# Sheet1.net
KiCad netlist of a schematic drawn in Altium Designer
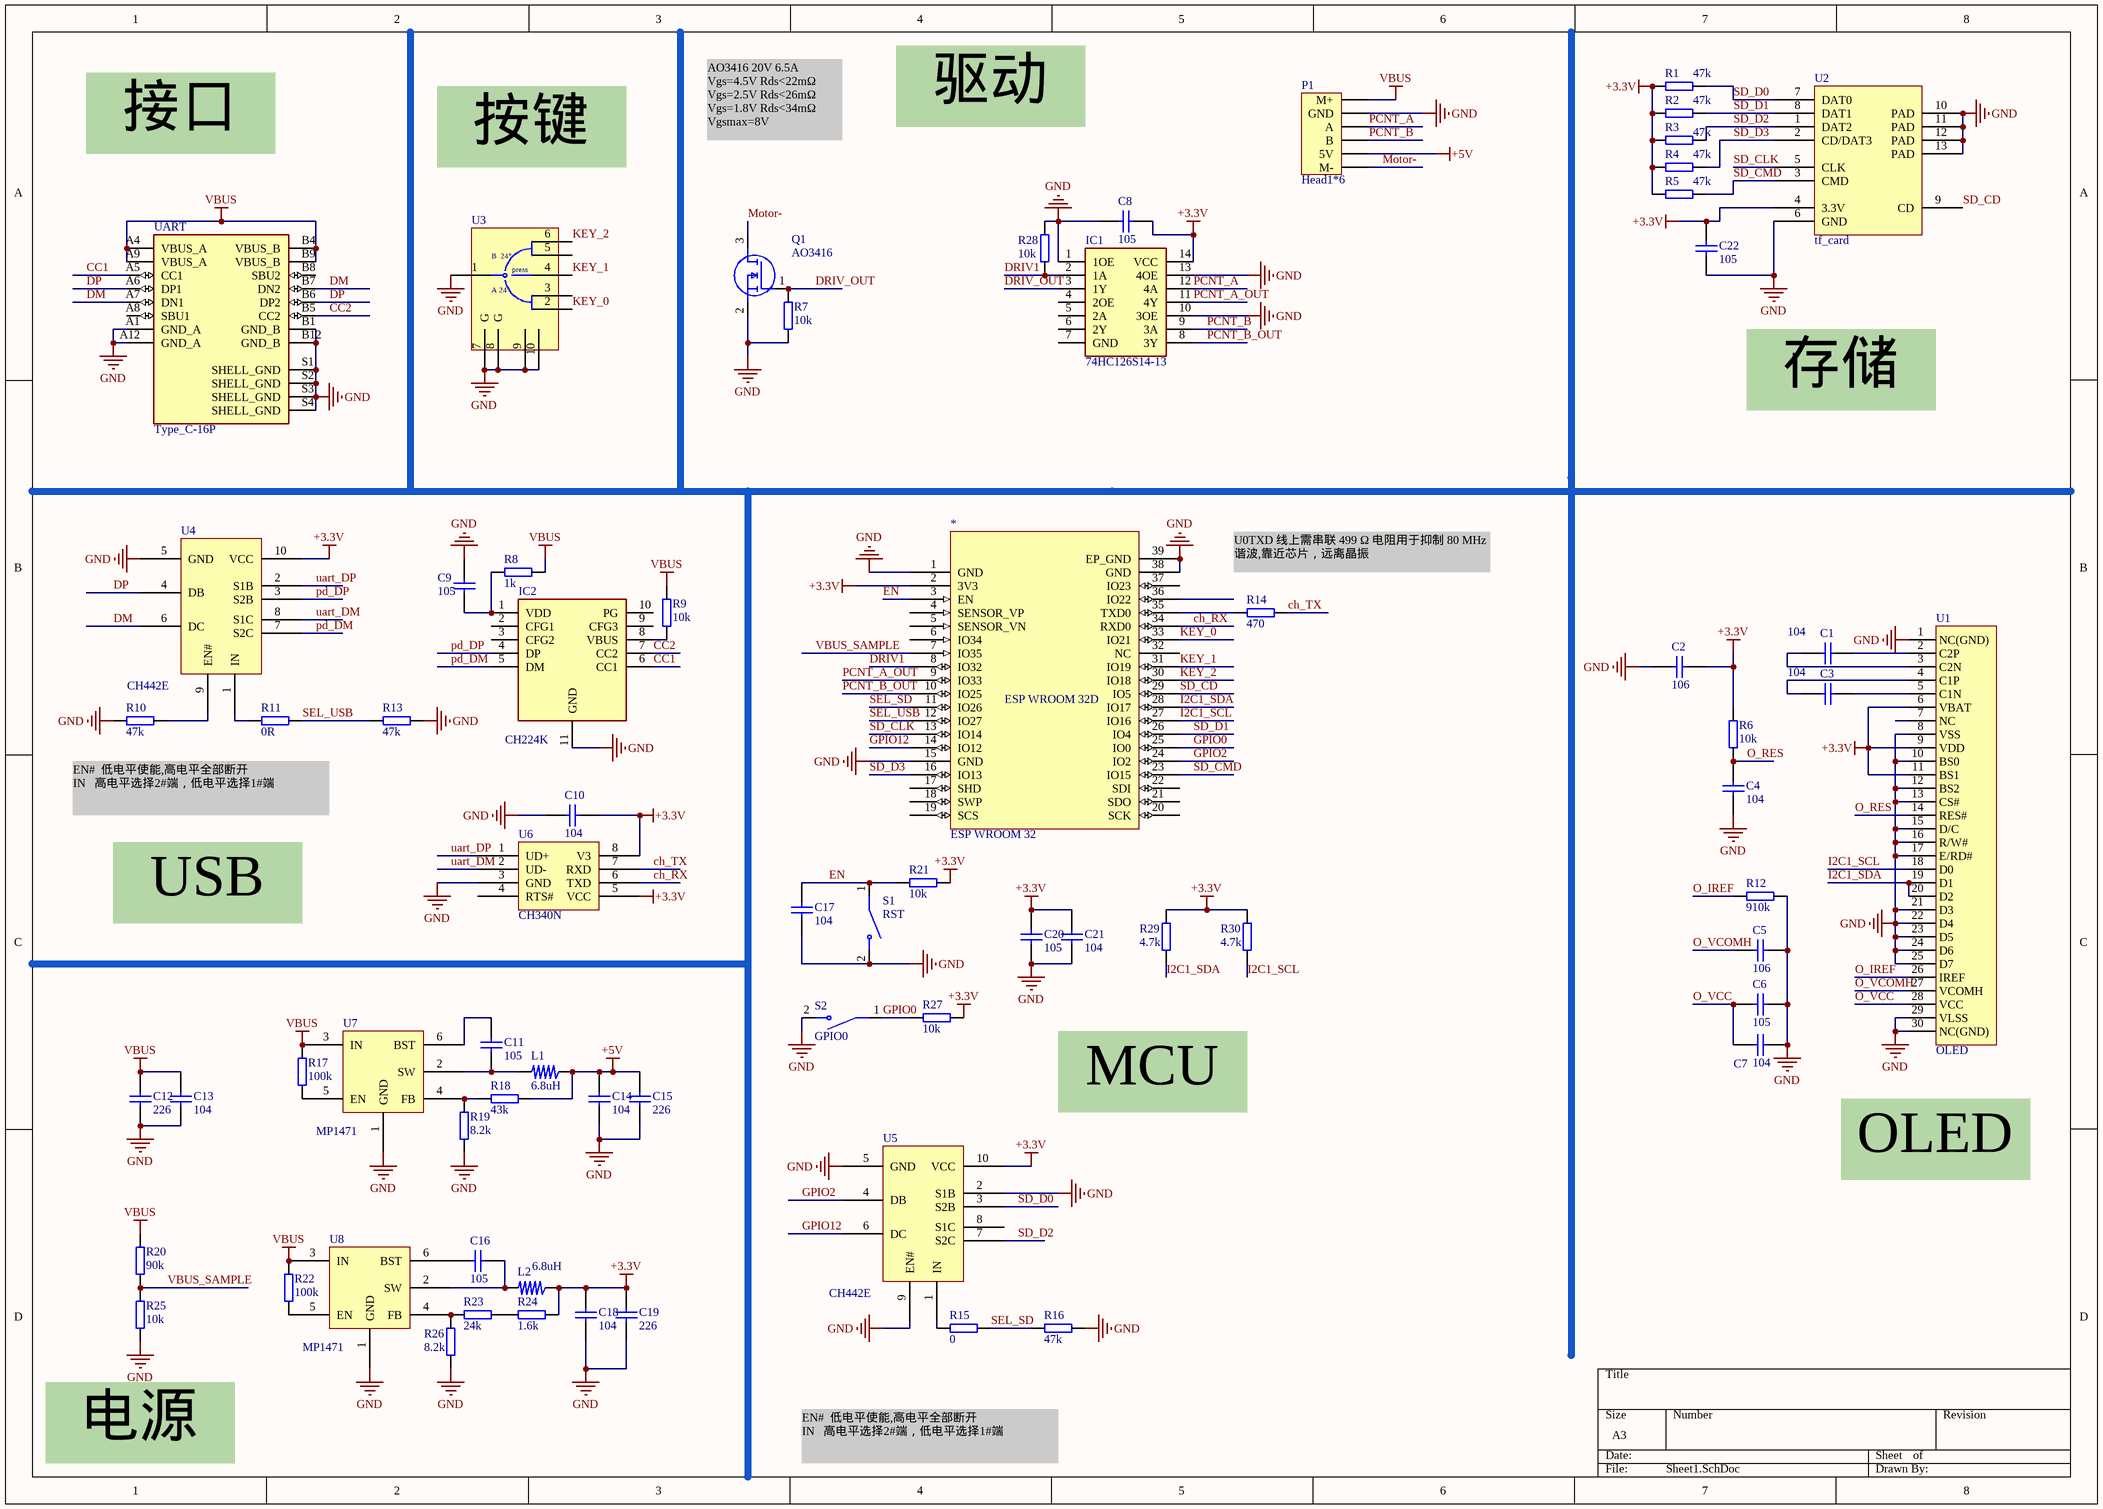
[diagram p0: Sheet1.SchDoc]

(export (version "E")
  (design (tool "Eeschema 10.0.6"))
  (components
    (comp (ref "*")
      (value "ESP WROOM 32")
      (footprint "ESP32-WROOM-32D")
      (libsource (lib "BuildDev") (part "ESP WROOM 32"))
    )
    (comp (ref "C1")
      (value "104")
      (footprint "CAPC1608[0603]")
      (description "Chip Capacitor, PSpice Model")
      (fields
        (field (name "TOLERANCE") "Y5V")
        (field (name "VOLTAGE") "3V")
        (field (name "PUBLISHER") "Altium Limited")
      )
      (libsource (lib "!)Miscellaneous Integrated Library") (part "Cap Chip 1"))
    )
    (comp (ref "C2")
      (value "106")
      (footprint "CAPC1608[0603]")
      (description "Chip Capacitor, PSpice Model")
      (fields
        (field (name "TOLERANCE") "Y5V")
        (field (name "VOLTAGE") "3V")
        (field (name "PUBLISHER") "Altium Limited")
      )
      (libsource (lib "!)Miscellaneous Integrated Library") (part "Cap Chip 1"))
    )
    (comp (ref "C3")
      (value "104")
      (footprint "CAPC1608[0603]")
      (description "Chip Capacitor, PSpice Model")
      (fields
        (field (name "TOLERANCE") "Y5V")
        (field (name "VOLTAGE") "3V")
        (field (name "PUBLISHER") "Altium Limited")
      )
      (libsource (lib "!)Miscellaneous Integrated Library") (part "Cap Chip 1"))
    )
    (comp (ref "C4")
      (value "104")
      (footprint "CAPC1608[0603]")
      (description "Chip Capacitor, PSpice Model")
      (fields
        (field (name "TOLERANCE") "Y5V")
        (field (name "VOLTAGE") "3V")
        (field (name "PUBLISHER") "Altium Limited")
      )
      (libsource (lib "!)Miscellaneous Integrated Library") (part "Cap Chip 1"))
    )
    (comp (ref "C5")
      (value "106")
      (footprint "CAPC1608[0603]")
      (description "Chip Capacitor, PSpice Model")
      (fields
        (field (name "TOLERANCE") "Y5V")
        (field (name "VOLTAGE") "3V")
        (field (name "PUBLISHER") "Altium Limited")
      )
      (libsource (lib "!)Miscellaneous Integrated Library") (part "Cap Chip 1"))
    )
    (comp (ref "C6")
      (value "105")
      (footprint "CAPC1608[0603]")
      (description "Chip Capacitor, PSpice Model")
      (fields
        (field (name "TOLERANCE") "Y5V")
        (field (name "VOLTAGE") "3V")
        (field (name "PUBLISHER") "Altium Limited")
      )
      (libsource (lib "!)Miscellaneous Integrated Library") (part "Cap Chip 1"))
    )
    (comp (ref "C7")
      (value "104")
      (footprint "CAPC1608[0603]")
      (description "Chip Capacitor, PSpice Model")
      (fields
        (field (name "TOLERANCE") "Y5V")
        (field (name "VOLTAGE") "3V")
        (field (name "PUBLISHER") "Altium Limited")
      )
      (libsource (lib "!)Miscellaneous Integrated Library") (part "Cap Chip 1"))
    )
    (comp (ref "C8")
      (value "105")
      (footprint "CAPC1608[0603]")
      (description "Chip Capacitor, PSpice Model")
      (fields
        (field (name "TOLERANCE") "Y5V")
        (field (name "VOLTAGE") "3V")
        (field (name "PUBLISHER") "Altium Limited")
      )
      (libsource (lib "!)Miscellaneous Integrated Library") (part "Cap Chip 1"))
    )
    (comp (ref "C9")
      (value "105")
      (footprint "CAPC1608[0603]")
      (description "Chip Capacitor, PSpice Model")
      (fields
        (field (name "TOLERANCE") "Y5V")
        (field (name "VOLTAGE") "3V")
        (field (name "PUBLISHER") "Altium Limited")
      )
      (libsource (lib "!)Miscellaneous Integrated Library") (part "Cap Chip 1"))
    )
    (comp (ref "C10")
      (value "104")
      (footprint "CAPC1608[0603]")
      (description "Chip Capacitor, PSpice Model")
      (fields
        (field (name "TOLERANCE") "Y5V")
        (field (name "VOLTAGE") "3V")
        (field (name "PUBLISHER") "Altium Limited")
      )
      (libsource (lib "!)Miscellaneous Integrated Library") (part "Cap Chip 1"))
    )
    (comp (ref "C11")
      (value "105")
      (footprint "CAPC1608[0603]")
      (description "Chip Capacitor, PSpice Model")
      (fields
        (field (name "TOLERANCE") "Y5V")
        (field (name "VOLTAGE") "3V")
        (field (name "PUBLISHER") "Altium Limited")
      )
      (libsource (lib "!)Miscellaneous Integrated Library") (part "Cap Chip 1"))
    )
    (comp (ref "C12")
      (value "226")
      (footprint "CAPC1608[0603]")
      (description "Chip Capacitor, PSpice Model")
      (fields
        (field (name "TOLERANCE") "Y5V")
        (field (name "VOLTAGE") "3V")
        (field (name "PUBLISHER") "Altium Limited")
      )
      (libsource (lib "!)Miscellaneous Integrated Library") (part "Cap Chip 1"))
    )
    (comp (ref "C13")
      (value "104")
      (footprint "CAPC1608[0603]")
      (description "Chip Capacitor, PSpice Model")
      (fields
        (field (name "TOLERANCE") "Y5V")
        (field (name "VOLTAGE") "3V")
        (field (name "PUBLISHER") "Altium Limited")
      )
      (libsource (lib "!)Miscellaneous Integrated Library") (part "Cap Chip 1"))
    )
    (comp (ref "C14")
      (value "104")
      (footprint "CAPC1608[0603]")
      (description "Chip Capacitor, PSpice Model")
      (fields
        (field (name "TOLERANCE") "Y5V")
        (field (name "VOLTAGE") "3V")
        (field (name "PUBLISHER") "Altium Limited")
      )
      (libsource (lib "!)Miscellaneous Integrated Library") (part "Cap Chip 1"))
    )
    (comp (ref "C15")
      (value "226")
      (footprint "CAPC1608[0603]")
      (description "Chip Capacitor, PSpice Model")
      (fields
        (field (name "TOLERANCE") "Y5V")
        (field (name "VOLTAGE") "3V")
        (field (name "PUBLISHER") "Altium Limited")
      )
      (libsource (lib "!)Miscellaneous Integrated Library") (part "Cap Chip 1"))
    )
    (comp (ref "C16")
      (value "105")
      (footprint "CAPC1608[0603]")
      (description "Chip Capacitor, PSpice Model")
      (fields
        (field (name "TOLERANCE") "Y5V")
        (field (name "VOLTAGE") "3V")
        (field (name "PUBLISHER") "Altium Limited")
      )
      (libsource (lib "!)Miscellaneous Integrated Library") (part "Cap Chip 1"))
    )
    (comp (ref "C17")
      (value "104")
      (footprint "CAPC1608[0603]")
      (description "Chip Capacitor, PSpice Model")
      (fields
        (field (name "TOLERANCE") "Y5V")
        (field (name "VOLTAGE") "3V")
        (field (name "PUBLISHER") "Altium Limited")
      )
      (libsource (lib "!)Miscellaneous Integrated Library") (part "Cap Chip 1"))
    )
    (comp (ref "C18")
      (value "104")
      (footprint "CAPC1608[0603]")
      (description "Chip Capacitor, PSpice Model")
      (fields
        (field (name "TOLERANCE") "Y5V")
        (field (name "VOLTAGE") "3V")
        (field (name "PUBLISHER") "Altium Limited")
      )
      (libsource (lib "!)Miscellaneous Integrated Library") (part "Cap Chip 1"))
    )
    (comp (ref "C19")
      (value "226")
      (footprint "CAPC1608[0603]")
      (description "Chip Capacitor, PSpice Model")
      (fields
        (field (name "TOLERANCE") "Y5V")
        (field (name "VOLTAGE") "3V")
        (field (name "PUBLISHER") "Altium Limited")
      )
      (libsource (lib "!)Miscellaneous Integrated Library") (part "Cap Chip 1"))
    )
    (comp (ref "C20")
      (value "105")
      (footprint "CAPC1608[0603]")
      (description "Chip Capacitor, PSpice Model")
      (fields
        (field (name "TOLERANCE") "Y5V")
        (field (name "VOLTAGE") "3V")
        (field (name "PUBLISHER") "Altium Limited")
      )
      (libsource (lib "!)Miscellaneous Integrated Library") (part "Cap Chip 1"))
    )
    (comp (ref "C21")
      (value "104")
      (footprint "CAPC1608[0603]")
      (description "Chip Capacitor, PSpice Model")
      (fields
        (field (name "TOLERANCE") "Y5V")
        (field (name "VOLTAGE") "3V")
        (field (name "PUBLISHER") "Altium Limited")
      )
      (libsource (lib "!)Miscellaneous Integrated Library") (part "Cap Chip 1"))
    )
    (comp (ref "C22")
      (value "105")
      (footprint "CAPC1608[0603]")
      (description "Chip Capacitor, PSpice Model")
      (fields
        (field (name "TOLERANCE") "Y5V")
        (field (name "VOLTAGE") "3V")
        (field (name "PUBLISHER") "Altium Limited")
      )
      (libsource (lib "!)Miscellaneous Integrated Library") (part "Cap Chip 1"))
    )
    (comp (ref "IC1")
      (value "74HC126S14-13")
      (footprint "SOIC127P600X173-14N")
      (description "Integrated Circuit")
      (fields (field (name "MOUSER PART NUMBER") "621-74HC126S14-13"))
      (libsource (lib "SamacSys") (part "74HC126S14-13"))
    )
    (comp (ref "IC2")
      (value "CH224K")
      (footprint "SOP100P600X180-11N")
      (description "Integrated Circuit")
      (libsource (lib "SamacSys") (part "CH224K"))
    )
    (comp (ref "L1") (value "6.8uH") (footprint "WHC0420") (libsource (lib "BuildDev") (part "L")))
    (comp (ref "L2") (value "6.8uH") (footprint "WHC0420") (libsource (lib "BuildDev") (part "L")))
    (comp (ref "P1")
      (value "Head1*6")
      (footprint "Header1*6")
      (libsource (lib "BuildDev") (part "Header1x6"))
    )
    (comp (ref "Q1")
      (value "AO3416")
      (footprint "SOT95P237X112-3N")
      (description "MOSFET (N-Channel)")
      (libsource (lib "SamacSys") (part "AO3416"))
    )
    (comp (ref "R1")
      (value "47k")
      (footprint "RESC1608[0603]")
      (description "Chip Resistor, PSpice Model, IPC PCB Library Drawing")
      (fields (field (name "TOLERANCE") "5%") (field (name "PUBLISHER") "Altium Limited"))
      (libsource (lib "!)Miscellaneous Integrated Library") (part "Res Chip 2p 1"))
    )
    (comp (ref "R2")
      (value "47k")
      (footprint "RESC1608[0603]")
      (description "Chip Resistor, PSpice Model, IPC PCB Library Drawing")
      (fields (field (name "TOLERANCE") "5%") (field (name "PUBLISHER") "Altium Limited"))
      (libsource (lib "!)Miscellaneous Integrated Library") (part "Res Chip 2p 1"))
    )
    (comp (ref "R3")
      (value "47k")
      (footprint "RESC1608[0603]")
      (description "Chip Resistor, PSpice Model, IPC PCB Library Drawing")
      (fields (field (name "TOLERANCE") "5%") (field (name "PUBLISHER") "Altium Limited"))
      (libsource (lib "!)Miscellaneous Integrated Library") (part "Res Chip 2p 1"))
    )
    (comp (ref "R4")
      (value "47k")
      (footprint "RESC1608[0603]")
      (description "Chip Resistor, PSpice Model, IPC PCB Library Drawing")
      (fields (field (name "TOLERANCE") "5%") (field (name "PUBLISHER") "Altium Limited"))
      (libsource (lib "!)Miscellaneous Integrated Library") (part "Res Chip 2p 1"))
    )
    (comp (ref "R5")
      (value "47k")
      (footprint "RESC1608[0603]")
      (description "Chip Resistor, PSpice Model, IPC PCB Library Drawing")
      (fields (field (name "TOLERANCE") "5%") (field (name "PUBLISHER") "Altium Limited"))
      (libsource (lib "!)Miscellaneous Integrated Library") (part "Res Chip 2p 1"))
    )
    (comp (ref "R6")
      (value "10k")
      (footprint "RESC1608[0603]")
      (description "Chip Resistor, PSpice Model, IPC PCB Library Drawing")
      (fields (field (name "TOLERANCE") "5%") (field (name "PUBLISHER") "Altium Limited"))
      (libsource (lib "!)Miscellaneous Integrated Library") (part "Res Chip 2p 1"))
    )
    (comp (ref "R7")
      (value "10k")
      (footprint "RESC1608[0603]")
      (description "Chip Resistor, PSpice Model, IPC PCB Library Drawing")
      (fields (field (name "TOLERANCE") "5%") (field (name "PUBLISHER") "Altium Limited"))
      (libsource (lib "!)Miscellaneous Integrated Library") (part "Res Chip 2p 1"))
    )
    (comp (ref "R8")
      (value "1k")
      (footprint "RESC1608[0603]")
      (description "Chip Resistor, PSpice Model, IPC PCB Library Drawing")
      (fields (field (name "TOLERANCE") "5%") (field (name "PUBLISHER") "Altium Limited"))
      (libsource (lib "!)Miscellaneous Integrated Library") (part "Res Chip 2p 1"))
    )
    (comp (ref "R9")
      (value "10k")
      (footprint "RESC1608[0603]")
      (description "Chip Resistor, PSpice Model, IPC PCB Library Drawing")
      (fields (field (name "TOLERANCE") "5%") (field (name "PUBLISHER") "Altium Limited"))
      (libsource (lib "!)Miscellaneous Integrated Library") (part "Res Chip 2p 1"))
    )
    (comp (ref "R10")
      (value "47k")
      (footprint "RESC1608[0603]")
      (description "Chip Resistor, PSpice Model, IPC PCB Library Drawing")
      (fields (field (name "TOLERANCE") "5%") (field (name "PUBLISHER") "Altium Limited"))
      (libsource (lib "!)Miscellaneous Integrated Library") (part "Res Chip 2p 1"))
    )
    (comp (ref "R11")
      (value "0R")
      (footprint "RESC1608[0603]")
      (description "Chip Resistor, PSpice Model, IPC PCB Library Drawing")
      (fields (field (name "TOLERANCE") "5%") (field (name "PUBLISHER") "Altium Limited"))
      (libsource (lib "!)Miscellaneous Integrated Library") (part "Res Chip 2p 1"))
    )
    (comp (ref "R12")
      (value "910k")
      (footprint "RESC1608[0603]")
      (description "Chip Resistor, PSpice Model, IPC PCB Library Drawing")
      (fields (field (name "TOLERANCE") "5%") (field (name "PUBLISHER") "Altium Limited"))
      (libsource (lib "!)Miscellaneous Integrated Library") (part "Res Chip 2p 1"))
    )
    (comp (ref "R13")
      (value "47k")
      (footprint "RESC1608[0603]")
      (description "Chip Resistor, PSpice Model, IPC PCB Library Drawing")
      (fields (field (name "TOLERANCE") "5%") (field (name "PUBLISHER") "Altium Limited"))
      (libsource (lib "!)Miscellaneous Integrated Library") (part "Res Chip 2p 1"))
    )
    (comp (ref "R14")
      (value "470")
      (footprint "RESC1608[0603]")
      (description "Chip Resistor, PSpice Model, IPC PCB Library Drawing")
      (fields (field (name "TOLERANCE") "5%") (field (name "PUBLISHER") "Altium Limited"))
      (libsource (lib "!)Miscellaneous Integrated Library") (part "Res Chip 2p 1"))
    )
    (comp (ref "R15")
      (value "0")
      (footprint "RESC1608[0603]")
      (description "Chip Resistor, PSpice Model, IPC PCB Library Drawing")
      (fields (field (name "TOLERANCE") "5%") (field (name "PUBLISHER") "Altium Limited"))
      (libsource (lib "!)Miscellaneous Integrated Library") (part "Res Chip 2p 1"))
    )
    (comp (ref "R16")
      (value "47k")
      (footprint "RESC1608[0603]")
      (description "Chip Resistor, PSpice Model, IPC PCB Library Drawing")
      (fields (field (name "TOLERANCE") "5%") (field (name "PUBLISHER") "Altium Limited"))
      (libsource (lib "!)Miscellaneous Integrated Library") (part "Res Chip 2p 1"))
    )
    (comp (ref "R17")
      (value "100k")
      (footprint "RESC1608[0603]")
      (description "Chip Resistor, PSpice Model, IPC PCB Library Drawing")
      (fields (field (name "TOLERANCE") "5%") (field (name "PUBLISHER") "Altium Limited"))
      (libsource (lib "!)Miscellaneous Integrated Library") (part "Res Chip 2p 1"))
    )
    (comp (ref "R18")
      (value "43k")
      (footprint "RESC1608[0603]")
      (description "Chip Resistor, PSpice Model, IPC PCB Library Drawing")
      (fields (field (name "TOLERANCE") "5%") (field (name "PUBLISHER") "Altium Limited"))
      (libsource (lib "!)Miscellaneous Integrated Library") (part "Res Chip 2p 1"))
    )
    (comp (ref "R19")
      (value "8.2k")
      (footprint "RESC1608[0603]")
      (description "Chip Resistor, PSpice Model, IPC PCB Library Drawing")
      (fields (field (name "TOLERANCE") "5%") (field (name "PUBLISHER") "Altium Limited"))
      (libsource (lib "!)Miscellaneous Integrated Library") (part "Res Chip 2p 1"))
    )
    (comp (ref "R20")
      (value "90k")
      (footprint "RESC1608[0603]")
      (description "Chip Resistor, PSpice Model, IPC PCB Library Drawing")
      (fields (field (name "TOLERANCE") "5%") (field (name "PUBLISHER") "Altium Limited"))
      (libsource (lib "!)Miscellaneous Integrated Library") (part "Res Chip 2p 1"))
    )
    (comp (ref "R21")
      (value "10k")
      (footprint "RESC1608[0603]")
      (description "Chip Resistor, PSpice Model, IPC PCB Library Drawing")
      (fields (field (name "TOLERANCE") "5%") (field (name "PUBLISHER") "Altium Limited"))
      (libsource (lib "!)Miscellaneous Integrated Library") (part "Res Chip 2p 1"))
    )
    (comp (ref "R22")
      (value "100k")
      (footprint "RESC1608[0603]")
      (description "Chip Resistor, PSpice Model, IPC PCB Library Drawing")
      (fields (field (name "TOLERANCE") "5%") (field (name "PUBLISHER") "Altium Limited"))
      (libsource (lib "!)Miscellaneous Integrated Library") (part "Res Chip 2p 1"))
    )
    (comp (ref "R23")
      (value "24k")
      (footprint "RESC1608[0603]")
      (description "Chip Resistor, PSpice Model, IPC PCB Library Drawing")
      (fields (field (name "TOLERANCE") "5%") (field (name "PUBLISHER") "Altium Limited"))
      (libsource (lib "!)Miscellaneous Integrated Library") (part "Res Chip 2p 1"))
    )
    (comp (ref "R24")
      (value "1.6k")
      (footprint "RESC1608[0603]")
      (description "Chip Resistor, PSpice Model, IPC PCB Library Drawing")
      (fields (field (name "TOLERANCE") "5%") (field (name "PUBLISHER") "Altium Limited"))
      (libsource (lib "!)Miscellaneous Integrated Library") (part "Res Chip 2p 1"))
    )
    (comp (ref "R25")
      (value "10k")
      (footprint "RESC1608[0603]")
      (description "Chip Resistor, PSpice Model, IPC PCB Library Drawing")
      (fields (field (name "TOLERANCE") "5%") (field (name "PUBLISHER") "Altium Limited"))
      (libsource (lib "!)Miscellaneous Integrated Library") (part "Res Chip 2p 1"))
    )
    (comp (ref "R26")
      (value "8.2k")
      (footprint "RESC1608[0603]")
      (description "Chip Resistor, PSpice Model, IPC PCB Library Drawing")
      (fields (field (name "TOLERANCE") "5%") (field (name "PUBLISHER") "Altium Limited"))
      (libsource (lib "!)Miscellaneous Integrated Library") (part "Res Chip 2p 1"))
    )
    (comp (ref "R27")
      (value "10k")
      (footprint "RESC1608[0603]")
      (description "Chip Resistor, PSpice Model, IPC PCB Library Drawing")
      (fields (field (name "TOLERANCE") "5%") (field (name "PUBLISHER") "Altium Limited"))
      (libsource (lib "!)Miscellaneous Integrated Library") (part "Res Chip 2p 1"))
    )
    (comp (ref "R28")
      (value "10k")
      (footprint "RESC1608[0603]")
      (description "Chip Resistor, PSpice Model, IPC PCB Library Drawing")
      (fields (field (name "TOLERANCE") "5%") (field (name "PUBLISHER") "Altium Limited"))
      (libsource (lib "!)Miscellaneous Integrated Library") (part "Res Chip 2p 1"))
    )
    (comp (ref "R29")
      (value "4.7k")
      (footprint "RESC1608[0603]")
      (description "Chip Resistor, PSpice Model, IPC PCB Library Drawing")
      (fields (field (name "TOLERANCE") "5%") (field (name "PUBLISHER") "Altium Limited"))
      (libsource (lib "!)Miscellaneous Integrated Library") (part "Res Chip 2p 1"))
    )
    (comp (ref "R30")
      (value "4.7k")
      (footprint "RESC1608[0603]")
      (description "Chip Resistor, PSpice Model, IPC PCB Library Drawing")
      (fields (field (name "TOLERANCE") "5%") (field (name "PUBLISHER") "Altium Limited"))
      (libsource (lib "!)Miscellaneous Integrated Library") (part "Res Chip 2p 1"))
    )
    (comp (ref "S1")
      (value "RST")
      (footprint "SW_B3U-1000P")
      (fields (field (name "MP") "B3U-1000P"))
      (libsource (lib "BuildDev") (part "SW2P"))
    )
    (comp (ref "S2")
      (value "GPIO0")
      (footprint "SW_B3U-1000P")
      (fields (field (name "MP") "B3U-1000P"))
      (libsource (lib "BuildDev") (part "SW2P"))
    )
    (comp (ref "U1") (value "OLED") (footprint "OLED-panel") (libsource (lib "BuildDev") (part "0.96寸OLED")))
    (comp (ref "U2") (value "tf_card") (footprint "TF-1") (libsource (lib "BuildDev") (part "TF- SDIO")))
    (comp (ref "U3") (value "拨码开关") (footprint "FS-1501S-02") (libsource (lib "BuildDev") (part "thumb key")))
    (comp (ref "U4") (value "CH442E") (footprint "MSOP-10") (libsource (lib "BuildDev") (part "CH442E")))
    (comp (ref "U5") (value "CH442E") (footprint "MSOP-10") (libsource (lib "BuildDev") (part "CH442E")))
    (comp (ref "U6")
      (value "CH340N")
      (footprint "SOP8")
      (description "USB to serial chip CH340N")
      (libsource (lib "BuildDev") (part "CH340N"))
    )
    (comp (ref "U7")
      (value "MP1471")
      (footprint "TSOT23-6")
      (description "4.7v-16V Input\r\n16V3A\r\n500K")
      (libsource (lib "BuildDev") (part "MP1471"))
    )
    (comp (ref "U8")
      (value "MP1471")
      (footprint "TSOT23-6")
      (description "4.7v-16V Input\r\n16V3A\r\n500K")
      (libsource (lib "BuildDev") (part "MP1471"))
    )
    (comp (ref "UART")
      (value "Type_C-16P")
      (footprint "VALCON_CSP-USC16-TR")
      (description "CSP-USC16-TR Valcon USB Type C Surface Mount PCB Socket")
      (fields (field (name "MP") "CSP-USC16-TR") (field (name "MF") "Valcon"))
      (libsource (lib "BuildDev") (part "Type_C-16P"))
    )
  )
  (nets
    (net (code "1") (name "+3.3V") (class "Default")
      (node (ref "*") (pin "2") (pinfunction "3V3_2") (pintype "passive"))
      (node (ref "C10") (pin "1") (pinfunction "1_1") (pintype "passive"))
      (node (ref "C18") (pin "1") (pinfunction "1_1") (pintype "passive"))
      (node (ref "C19") (pin "1") (pinfunction "1_1") (pintype "passive"))
      (node (ref "C2") (pin "1") (pinfunction "1_1") (pintype "passive"))
      (node (ref "C20") (pin "1") (pinfunction "1_1") (pintype "passive"))
      (node (ref "C21") (pin "1") (pinfunction "1_1") (pintype "passive"))
      (node (ref "C22") (pin "2") (pinfunction "2_2") (pintype "passive"))
      (node (ref "C8") (pin "2") (pinfunction "2_2") (pintype "passive"))
      (node (ref "IC1") (pin "14") (pinfunction "VCC_14") (pintype "passive"))
      (node (ref "L2") (pin "1") (pinfunction "1_1") (pintype "passive"))
      (node (ref "R1") (pin "2") (pinfunction "2_2") (pintype "passive"))
      (node (ref "R2") (pin "2") (pinfunction "2_2") (pintype "passive"))
      (node (ref "R21") (pin "1") (pinfunction "1_1") (pintype "passive"))
      (node (ref "R24") (pin "2") (pinfunction "2_2") (pintype "passive"))
      (node (ref "R27") (pin "1") (pinfunction "1_1") (pintype "passive"))
      (node (ref "R29") (pin "1") (pinfunction "1_1") (pintype "passive"))
      (node (ref "R3") (pin "2") (pinfunction "2_2") (pintype "passive"))
      (node (ref "R30") (pin "1") (pinfunction "1_1") (pintype "passive"))
      (node (ref "R4") (pin "2") (pinfunction "2_2") (pintype "passive"))
      (node (ref "R5") (pin "2") (pinfunction "2_2") (pintype "passive"))
      (node (ref "R6") (pin "1") (pinfunction "1_1") (pintype "passive"))
      (node (ref "U1") (pin "11") (pinfunction "BS1_11") (pintype "passive"))
      (node (ref "U1") (pin "6") (pinfunction "VBAT_6") (pintype "passive"))
      (node (ref "U1") (pin "9") (pinfunction "VDD_9") (pintype "passive"))
      (node (ref "U2") (pin "4") (pinfunction "3.3V_4") (pintype "passive"))
      (node (ref "U4") (pin "10") (pinfunction "VCC_10") (pintype "passive"))
      (node (ref "U5") (pin "10") (pinfunction "VCC_10") (pintype "passive"))
      (node (ref "U6") (pin "5") (pinfunction "VCC_5") (pintype "passive"))
      (node (ref "U6") (pin "8") (pinfunction "V3_8") (pintype "passive"))
    )
    (net (code "2") (name "+5V") (class "Default")
      (node (ref "C14") (pin "1") (pinfunction "1_1") (pintype "passive"))
      (node (ref "C15") (pin "1") (pinfunction "1_1") (pintype "passive"))
      (node (ref "L1") (pin "1") (pinfunction "1_1") (pintype "passive"))
      (node (ref "P1") (pin "5") (pinfunction "5V_5") (pintype "passive"))
      (node (ref "R18") (pin "2") (pinfunction "2_2") (pintype "passive"))
    )
    (net (code "3") (name "/CC1") (class "Default")
      (node (ref "IC2") (pin "6") (pinfunction "CC1_6") (pintype "passive"))
      (node (ref "UART") (pin "A5") (pinfunction "CC1_A5") (pintype "bidirectional"))
    )
    (net (code "4") (name "/CC2") (class "Default")
      (node (ref "IC2") (pin "7") (pinfunction "CC2_7") (pintype "passive"))
      (node (ref "UART") (pin "B5") (pinfunction "CC2_B5") (pintype "bidirectional"))
    )
    (net (code "5") (name "/DM") (class "Default")
      (node (ref "U4") (pin "6") (pinfunction "DC_6") (pintype "passive"))
      (node (ref "UART") (pin "A7") (pinfunction "DN1_A7") (pintype "bidirectional"))
      (node (ref "UART") (pin "B7") (pinfunction "DN2_B7") (pintype "bidirectional"))
    )
    (net (code "6") (name "/DP") (class "Default")
      (node (ref "U4") (pin "4") (pinfunction "DB_4") (pintype "passive"))
      (node (ref "UART") (pin "A6") (pinfunction "DP1_A6") (pintype "bidirectional"))
      (node (ref "UART") (pin "B6") (pinfunction "DP2_B6") (pintype "bidirectional"))
    )
    (net (code "7") (name "/DRIV1") (class "Default")
      (node (ref "*") (pin "8") (pinfunction "IO32_8") (pintype "bidirectional"))
      (node (ref "IC1") (pin "2") (pinfunction "1A_2") (pintype "passive"))
      (node (ref "R28") (pin "2") (pinfunction "2_2") (pintype "passive"))
    )
    (net (code "8") (name "/DRIV_OUT") (class "Default")
      (node (ref "IC1") (pin "3") (pinfunction "1Y_3") (pintype "passive"))
      (node (ref "Q1") (pin "1") (pinfunction "G_1") (pintype "passive"))
      (node (ref "R7") (pin "2") (pinfunction "2_2") (pintype "passive"))
    )
    (net (code "9") (name "/EN") (class "Default")
      (node (ref "*") (pin "3") (pinfunction "EN_3") (pintype "input"))
      (node (ref "C17") (pin "1") (pinfunction "1_1") (pintype "passive"))
      (node (ref "R21") (pin "2") (pinfunction "2_2") (pintype "passive"))
      (node (ref "S1") (pin "1") (pinfunction "1_1") (pintype "passive"))
    )
    (net (code "10") (name "/GPIO0") (class "Default")
      (node (ref "*") (pin "25") (pinfunction "IO0_25") (pintype "bidirectional"))
      (node (ref "R27") (pin "2") (pinfunction "2_2") (pintype "passive"))
      (node (ref "S2") (pin "1") (pinfunction "1_1") (pintype "passive"))
    )
    (net (code "11") (name "/GPIO2") (class "Default")
      (node (ref "*") (pin "24") (pinfunction "IO2_24") (pintype "bidirectional"))
      (node (ref "U5") (pin "4") (pinfunction "DB_4") (pintype "passive"))
    )
    (net (code "12") (name "/GPIO12") (class "Default")
      (node (ref "*") (pin "14") (pinfunction "IO12_14") (pintype "bidirectional"))
      (node (ref "U5") (pin "6") (pinfunction "DC_6") (pintype "passive"))
    )
    (net (code "13") (name "/I2C1_SCL") (class "Default")
      (node (ref "*") (pin "27") (pinfunction "IO16_27") (pintype "bidirectional"))
      (node (ref "R30") (pin "2") (pinfunction "2_2") (pintype "passive"))
      (node (ref "U1") (pin "18") (pinfunction "D0_18") (pintype "passive"))
    )
    (net (code "14") (name "/I2C1_SDA") (class "Default")
      (node (ref "*") (pin "28") (pinfunction "IO17_28") (pintype "bidirectional"))
      (node (ref "R29") (pin "2") (pinfunction "2_2") (pintype "passive"))
      (node (ref "U1") (pin "19") (pinfunction "D1_19") (pintype "passive"))
      (node (ref "U1") (pin "20") (pinfunction "D2_20") (pintype "passive"))
    )
    (net (code "15") (name "/KEY_0") (class "Default")
      (node (ref "*") (pin "33") (pinfunction "IO21_33") (pintype "bidirectional"))
      (node (ref "U3") (pin "2") (pintype "passive"))
    )
    (net (code "16") (name "/KEY_1") (class "Default")
      (node (ref "*") (pin "31") (pinfunction "IO19_31") (pintype "bidirectional"))
      (node (ref "U3") (pin "4") (pintype "passive"))
    )
    (net (code "17") (name "/KEY_2") (class "Default")
      (node (ref "*") (pin "30") (pinfunction "IO18_30") (pintype "bidirectional"))
      (node (ref "U3") (pin "6") (pintype "passive"))
    )
    (net (code "18") (name "/Motor-") (class "Default")
      (node (ref "P1") (pin "6") (pinfunction "M-_6") (pintype "passive"))
      (node (ref "Q1") (pin "3") (pinfunction "D_3") (pintype "passive"))
    )
    (net (code "19") (name "/O_IREF") (class "Default")
      (node (ref "R12") (pin "1") (pinfunction "1_1") (pintype "passive"))
      (node (ref "U1") (pin "26") (pinfunction "IREF_26") (pintype "passive"))
    )
    (net (code "20") (name "/O_RES") (class "Default")
      (node (ref "C4") (pin "1") (pinfunction "1_1") (pintype "passive"))
      (node (ref "R6") (pin "2") (pinfunction "2_2") (pintype "passive"))
      (node (ref "U1") (pin "14") (pinfunction "RES#_14") (pintype "passive"))
    )
    (net (code "21") (name "/O_VCC") (class "Default")
      (node (ref "C6") (pin "2") (pinfunction "2_2") (pintype "passive"))
      (node (ref "C7") (pin "1") (pinfunction "1_1") (pintype "passive"))
      (node (ref "U1") (pin "28") (pinfunction "VCC_28") (pintype "passive"))
    )
    (net (code "22") (name "/O_VCOMH") (class "Default")
      (node (ref "C5") (pin "1") (pinfunction "1_1") (pintype "passive"))
      (node (ref "U1") (pin "27") (pinfunction "VCOMH_27") (pintype "passive"))
    )
    (net (code "23") (name "/PCNT_A") (class "Default")
      (node (ref "IC1") (pin "12") (pinfunction "4A_12") (pintype "passive"))
      (node (ref "P1") (pin "3") (pinfunction "A_3") (pintype "passive"))
    )
    (net (code "24") (name "/PCNT_A_OUT") (class "Default")
      (node (ref "*") (pin "9") (pinfunction "IO33_9") (pintype "bidirectional"))
      (node (ref "IC1") (pin "11") (pinfunction "4Y_11") (pintype "passive"))
    )
    (net (code "25") (name "/PCNT_B") (class "Default")
      (node (ref "IC1") (pin "9") (pinfunction "3A_9") (pintype "passive"))
      (node (ref "P1") (pin "4") (pinfunction "B_4") (pintype "passive"))
    )
    (net (code "26") (name "/PCNT_B_OUT") (class "Default")
      (node (ref "*") (pin "10") (pinfunction "IO25_10") (pintype "bidirectional"))
      (node (ref "IC1") (pin "8") (pinfunction "3Y_8") (pintype "passive"))
    )
    (net (code "27") (name "/SD_CD") (class "Default")
      (node (ref "*") (pin "29") (pinfunction "IO5_29") (pintype "bidirectional"))
      (node (ref "U2") (pin "9") (pinfunction "CD_9") (pintype "passive"))
    )
    (net (code "28") (name "/SD_CLK") (class "Default")
      (node (ref "*") (pin "13") (pinfunction "IO14_13") (pintype "bidirectional"))
      (node (ref "U2") (pin "5") (pinfunction "CLK_5") (pintype "passive"))
    )
    (net (code "29") (name "/SD_CMD") (class "Default")
      (node (ref "*") (pin "23") (pinfunction "IO15_23") (pintype "bidirectional"))
      (node (ref "R5") (pin "1") (pinfunction "1_1") (pintype "passive"))
      (node (ref "U2") (pin "3") (pinfunction "CMD_3") (pintype "passive"))
    )
    (net (code "30") (name "/SD_D0") (class "Default")
      (node (ref "R1") (pin "1") (pinfunction "1_1") (pintype "passive"))
      (node (ref "U2") (pin "7") (pinfunction "DAT0_7") (pintype "passive"))
      (node (ref "U5") (pin "3") (pinfunction "S2B_3") (pintype "passive"))
    )
    (net (code "31") (name "/SD_D1") (class "Default")
      (node (ref "*") (pin "26") (pinfunction "IO4_26") (pintype "bidirectional"))
      (node (ref "R2") (pin "1") (pinfunction "1_1") (pintype "passive"))
      (node (ref "U2") (pin "8") (pinfunction "DAT1_8") (pintype "passive"))
    )
    (net (code "32") (name "/SD_D2") (class "Default")
      (node (ref "R3") (pin "1") (pinfunction "1_1") (pintype "passive"))
      (node (ref "U2") (pin "1") (pinfunction "DAT2_1") (pintype "passive"))
      (node (ref "U5") (pin "7") (pinfunction "S2C_7") (pintype "passive"))
    )
    (net (code "33") (name "/SD_D3") (class "Default")
      (node (ref "*") (pin "16") (pinfunction "IO13_16") (pintype "bidirectional"))
      (node (ref "R4") (pin "1") (pinfunction "1_1") (pintype "passive"))
      (node (ref "U2") (pin "2") (pinfunction "CD/DAT3_2") (pintype "passive"))
    )
    (net (code "34") (name "/SEL_SD") (class "Default")
      (node (ref "*") (pin "11") (pinfunction "IO26_11") (pintype "bidirectional"))
      (node (ref "R15") (pin "1") (pinfunction "1_1") (pintype "passive"))
      (node (ref "R16") (pin "2") (pinfunction "2_2") (pintype "passive"))
    )
    (net (code "35") (name "/SEL_USB") (class "Default")
      (node (ref "*") (pin "12") (pinfunction "IO27_12") (pintype "bidirectional"))
      (node (ref "R11") (pin "1") (pinfunction "1_1") (pintype "passive"))
      (node (ref "R13") (pin "2") (pinfunction "2_2") (pintype "passive"))
    )
    (net (code "36") (name "/VBUS_SAMPLE") (class "Default")
      (node (ref "*") (pin "7") (pinfunction "IO35_7") (pintype "input"))
      (node (ref "R20") (pin "2") (pinfunction "2_2") (pintype "passive"))
      (node (ref "R25") (pin "1") (pinfunction "1_1") (pintype "passive"))
    )
    (net (code "37") (name "/ch_RX") (class "Default")
      (node (ref "*") (pin "34") (pinfunction "RXD0_34") (pintype "bidirectional"))
      (node (ref "U6") (pin "6") (pinfunction "TXD_6") (pintype "passive"))
    )
    (net (code "38") (name "/ch_TX") (class "Default")
      (node (ref "R14") (pin "1") (pinfunction "1_1") (pintype "passive"))
      (node (ref "U6") (pin "7") (pinfunction "RXD_7") (pintype "passive"))
    )
    (net (code "39") (name "/pd_DM") (class "Default")
      (node (ref "IC2") (pin "5") (pinfunction "DM_5") (pintype "passive"))
      (node (ref "U4") (pin "7") (pinfunction "S2C_7") (pintype "passive"))
    )
    (net (code "40") (name "/pd_DP") (class "Default")
      (node (ref "IC2") (pin "4") (pinfunction "DP_4") (pintype "passive"))
      (node (ref "U4") (pin "3") (pinfunction "S2B_3") (pintype "passive"))
    )
    (net (code "41") (name "/uart_DM") (class "Default")
      (node (ref "U4") (pin "8") (pinfunction "S1C_8") (pintype "passive"))
      (node (ref "U6") (pin "2") (pinfunction "UD-_2") (pintype "passive"))
    )
    (net (code "42") (name "/uart_DP") (class "Default")
      (node (ref "U4") (pin "2") (pinfunction "S1B_2") (pintype "passive"))
      (node (ref "U6") (pin "1") (pinfunction "UD+_1") (pintype "passive"))
    )
    (net (code "43") (name "GND") (class "Default")
      (node (ref "*") (pin "1") (pinfunction "GND_1") (pintype "passive"))
      (node (ref "*") (pin "15") (pinfunction "GND_15") (pintype "passive"))
      (node (ref "*") (pin "38") (pinfunction "GND_38") (pintype "passive"))
      (node (ref "*") (pin "39") (pinfunction "EP_GND_39") (pintype "passive"))
      (node (ref "C10") (pin "2") (pinfunction "2_2") (pintype "passive"))
      (node (ref "C12") (pin "2") (pinfunction "2_2") (pintype "passive"))
      (node (ref "C13") (pin "2") (pinfunction "2_2") (pintype "passive"))
      (node (ref "C14") (pin "2") (pinfunction "2_2") (pintype "passive"))
      (node (ref "C15") (pin "2") (pinfunction "2_2") (pintype "passive"))
      (node (ref "C17") (pin "2") (pinfunction "2_2") (pintype "passive"))
      (node (ref "C18") (pin "2") (pinfunction "2_2") (pintype "passive"))
      (node (ref "C19") (pin "2") (pinfunction "2_2") (pintype "passive"))
      (node (ref "C2") (pin "2") (pinfunction "2_2") (pintype "passive"))
      (node (ref "C20") (pin "2") (pinfunction "2_2") (pintype "passive"))
      (node (ref "C21") (pin "2") (pinfunction "2_2") (pintype "passive"))
      (node (ref "C22") (pin "1") (pinfunction "1_1") (pintype "passive"))
      (node (ref "C4") (pin "2") (pinfunction "2_2") (pintype "passive"))
      (node (ref "C5") (pin "2") (pinfunction "2_2") (pintype "passive"))
      (node (ref "C6") (pin "1") (pinfunction "1_1") (pintype "passive"))
      (node (ref "C7") (pin "2") (pinfunction "2_2") (pintype "passive"))
      (node (ref "C8") (pin "1") (pinfunction "1_1") (pintype "passive"))
      (node (ref "C9") (pin "1") (pinfunction "1_1") (pintype "passive"))
      (node (ref "IC1") (pin "1") (pinfunction "1OE_1") (pintype "passive"))
      (node (ref "IC1") (pin "10") (pinfunction "3OE_10") (pintype "passive"))
      (node (ref "IC1") (pin "13") (pinfunction "4OE_13") (pintype "passive"))
      (node (ref "IC2") (pin "11") (pinfunction "GND_11") (pintype "passive"))
      (node (ref "P1") (pin "2") (pinfunction "GND_2") (pintype "passive"))
      (node (ref "Q1") (pin "2") (pinfunction "S_2") (pintype "passive"))
      (node (ref "R10") (pin "2") (pinfunction "2_2") (pintype "passive"))
      (node (ref "R12") (pin "2") (pinfunction "2_2") (pintype "passive"))
      (node (ref "R13") (pin "1") (pinfunction "1_1") (pintype "passive"))
      (node (ref "R16") (pin "1") (pinfunction "1_1") (pintype "passive"))
      (node (ref "R19") (pin "2") (pinfunction "2_2") (pintype "passive"))
      (node (ref "R25") (pin "2") (pinfunction "2_2") (pintype "passive"))
      (node (ref "R26") (pin "2") (pinfunction "2_2") (pintype "passive"))
      (node (ref "R28") (pin "1") (pinfunction "1_1") (pintype "passive"))
      (node (ref "R7") (pin "1") (pinfunction "1_1") (pintype "passive"))
      (node (ref "S1") (pin "2") (pinfunction "2_2") (pintype "passive"))
      (node (ref "S2") (pin "2") (pinfunction "2_2") (pintype "passive"))
      (node (ref "U1") (pin "1") (pinfunction "NC(GND)_1") (pintype "passive"))
      (node (ref "U1") (pin "10") (pinfunction "BS0_10") (pintype "passive"))
      (node (ref "U1") (pin "12") (pinfunction "BS2_12") (pintype "passive"))
      (node (ref "U1") (pin "13") (pinfunction "CS#_13") (pintype "passive"))
      (node (ref "U1") (pin "15") (pinfunction "D/C_15") (pintype "passive"))
      (node (ref "U1") (pin "16") (pinfunction "R/W#_16") (pintype "passive"))
      (node (ref "U1") (pin "17") (pinfunction "E/RD#_17") (pintype "passive"))
      (node (ref "U1") (pin "21") (pinfunction "D3_21") (pintype "passive"))
      (node (ref "U1") (pin "22") (pinfunction "D4_22") (pintype "passive"))
      (node (ref "U1") (pin "23") (pinfunction "D5_23") (pintype "passive"))
      (node (ref "U1") (pin "24") (pinfunction "D6_24") (pintype "passive"))
      (node (ref "U1") (pin "25") (pinfunction "D7_25") (pintype "passive"))
      (node (ref "U1") (pin "29") (pinfunction "VLSS_29") (pintype "passive"))
      (node (ref "U1") (pin "30") (pinfunction "NC(GND)_30") (pintype "passive"))
      (node (ref "U1") (pin "8") (pinfunction "VSS_8") (pintype "passive"))
      (node (ref "U2") (pin "10") (pinfunction "PAD_10") (pintype "passive"))
      (node (ref "U2") (pin "11") (pinfunction "PAD_11") (pintype "passive"))
      (node (ref "U2") (pin "12") (pinfunction "PAD_12") (pintype "passive"))
      (node (ref "U2") (pin "13") (pinfunction "PAD_13") (pintype "passive"))
      (node (ref "U2") (pin "6") (pinfunction "GND_6") (pintype "passive"))
      (node (ref "U3") (pin "1") (pintype "passive"))
      (node (ref "U3") (pin "10") (pintype "passive"))
      (node (ref "U3") (pin "7") (pinfunction "G_7") (pintype "passive"))
      (node (ref "U3") (pin "8") (pinfunction "G_8") (pintype "passive"))
      (node (ref "U3") (pin "9") (pintype "passive"))
      (node (ref "U4") (pin "5") (pinfunction "GND_5") (pintype "passive"))
      (node (ref "U5") (pin "2") (pinfunction "S1B_2") (pintype "passive"))
      (node (ref "U5") (pin "5") (pinfunction "GND_5") (pintype "passive"))
      (node (ref "U5") (pin "9") (pinfunction "EN#_9") (pintype "passive"))
      (node (ref "U6") (pin "3") (pinfunction "GND_3") (pintype "passive"))
      (node (ref "U7") (pin "1") (pinfunction "GND_1") (pintype "passive"))
      (node (ref "U8") (pin "1") (pinfunction "GND_1") (pintype "passive"))
      (node (ref "UART") (pin "A1") (pinfunction "GND_A_A1") (pintype "power_in"))
      (node (ref "UART") (pin "A12") (pinfunction "GND_A_A12") (pintype "power_in"))
      (node (ref "UART") (pin "B1") (pinfunction "GND_B_B1") (pintype "power_in"))
      (node (ref "UART") (pin "B12") (pinfunction "GND_B_B12") (pintype "power_in"))
      (node (ref "UART") (pin "S1") (pinfunction "SHELL_GND_S1") (pintype "power_in"))
      (node (ref "UART") (pin "S2") (pinfunction "SHELL_GND_S2") (pintype "power_in"))
      (node (ref "UART") (pin "S3") (pinfunction "SHELL_GND_S3") (pintype "power_in"))
      (node (ref "UART") (pin "S4") (pinfunction "SHELL_GND_S4") (pintype "power_in"))
    )
    (net (code "44") (name "Net-(*-TXD0)") (class "Default")
      (node (ref "*") (pin "35") (pinfunction "TXD0_35") (pintype "bidirectional"))
      (node (ref "R14") (pin "2") (pinfunction "2_2") (pintype "passive"))
    )
    (net (code "45") (name "Net-(IC2-VBUS)") (class "Default")
      (node (ref "IC2") (pin "8") (pinfunction "VBUS_8") (pintype "passive"))
      (node (ref "R9") (pin "1") (pinfunction "1_1") (pintype "passive"))
    )
    (net (code "46") (name "Net-(IC2-VDD)") (class "Default")
      (node (ref "C9") (pin "2") (pinfunction "2_2") (pintype "passive"))
      (node (ref "IC2") (pin "1") (pinfunction "VDD_1") (pintype "passive"))
      (node (ref "R8") (pin "1") (pinfunction "1_1") (pintype "passive"))
    )
    (net (code "47") (name "Net-(R23-Pad2)") (class "Default")
      (node (ref "R23") (pin "2") (pinfunction "2_2") (pintype "passive"))
      (node (ref "R24") (pin "1") (pinfunction "1_1") (pintype "passive"))
    )
    (net (code "48") (name "Net-(U1-C1N)") (class "Default")
      (node (ref "C3") (pin "2") (pinfunction "2_2") (pintype "passive"))
      (node (ref "U1") (pin "5") (pinfunction "C1N_5") (pintype "passive"))
    )
    (net (code "49") (name "Net-(U1-C1P)") (class "Default")
      (node (ref "C3") (pin "1") (pinfunction "1_1") (pintype "passive"))
      (node (ref "U1") (pin "4") (pinfunction "C1P_4") (pintype "passive"))
    )
    (net (code "50") (name "Net-(U1-C2N)") (class "Default")
      (node (ref "C1") (pin "1") (pinfunction "1_1") (pintype "passive"))
      (node (ref "U1") (pin "3") (pinfunction "C2N_3") (pintype "passive"))
    )
    (net (code "51") (name "Net-(U1-C2P)") (class "Default")
      (node (ref "C1") (pin "2") (pinfunction "2_2") (pintype "passive"))
      (node (ref "U1") (pin "2") (pinfunction "C2P_2") (pintype "passive"))
    )
    (net (code "52") (name "Net-(U4-EN#)") (class "Default")
      (node (ref "R10") (pin "1") (pinfunction "1_1") (pintype "passive"))
      (node (ref "U4") (pin "9") (pinfunction "EN#_9") (pintype "passive"))
    )
    (net (code "53") (name "Net-(U4-IN)") (class "Default")
      (node (ref "R11") (pin "2") (pinfunction "2_2") (pintype "passive"))
      (node (ref "U4") (pin "1") (pinfunction "IN_1") (pintype "passive"))
    )
    (net (code "54") (name "Net-(U5-IN)") (class "Default")
      (node (ref "R15") (pin "2") (pinfunction "2_2") (pintype "passive"))
      (node (ref "U5") (pin "1") (pinfunction "IN_1") (pintype "passive"))
    )
    (net (code "55") (name "Net-(U7-BST)") (class "Default")
      (node (ref "C11") (pin "1") (pinfunction "1_1") (pintype "passive"))
      (node (ref "U7") (pin "6") (pinfunction "BST_6") (pintype "passive"))
    )
    (net (code "56") (name "Net-(U7-EN)") (class "Default")
      (node (ref "R17") (pin "2") (pinfunction "2_2") (pintype "passive"))
      (node (ref "U7") (pin "5") (pinfunction "EN_5") (pintype "passive"))
    )
    (net (code "57") (name "Net-(U7-FB)") (class "Default")
      (node (ref "R18") (pin "1") (pinfunction "1_1") (pintype "passive"))
      (node (ref "R19") (pin "1") (pinfunction "1_1") (pintype "passive"))
      (node (ref "U7") (pin "4") (pinfunction "FB_4") (pintype "passive"))
    )
    (net (code "58") (name "Net-(U7-SW)") (class "Default")
      (node (ref "C11") (pin "2") (pinfunction "2_2") (pintype "passive"))
      (node (ref "L1") (pin "2") (pinfunction "2_2") (pintype "passive"))
      (node (ref "U7") (pin "2") (pinfunction "SW_2") (pintype "passive"))
    )
    (net (code "59") (name "Net-(U8-BST)") (class "Default")
      (node (ref "C16") (pin "1") (pinfunction "1_1") (pintype "passive"))
      (node (ref "U8") (pin "6") (pinfunction "BST_6") (pintype "passive"))
    )
    (net (code "60") (name "Net-(U8-EN)") (class "Default")
      (node (ref "R22") (pin "2") (pinfunction "2_2") (pintype "passive"))
      (node (ref "U8") (pin "5") (pinfunction "EN_5") (pintype "passive"))
    )
    (net (code "61") (name "Net-(U8-FB)") (class "Default")
      (node (ref "R23") (pin "1") (pinfunction "1_1") (pintype "passive"))
      (node (ref "R26") (pin "1") (pinfunction "1_1") (pintype "passive"))
      (node (ref "U8") (pin "4") (pinfunction "FB_4") (pintype "passive"))
    )
    (net (code "62") (name "Net-(U8-SW)") (class "Default")
      (node (ref "C16") (pin "2") (pinfunction "2_2") (pintype "passive"))
      (node (ref "L2") (pin "2") (pinfunction "2_2") (pintype "passive"))
      (node (ref "U8") (pin "2") (pinfunction "SW_2") (pintype "passive"))
    )
    (net (code "63") (name "VBUS") (class "Default")
      (node (ref "C12") (pin "1") (pinfunction "1_1") (pintype "passive"))
      (node (ref "C13") (pin "1") (pinfunction "1_1") (pintype "passive"))
      (node (ref "P1") (pin "1") (pinfunction "M+_1") (pintype "passive"))
      (node (ref "R17") (pin "1") (pinfunction "1_1") (pintype "passive"))
      (node (ref "R20") (pin "1") (pinfunction "1_1") (pintype "passive"))
      (node (ref "R22") (pin "1") (pinfunction "1_1") (pintype "passive"))
      (node (ref "R8") (pin "2") (pinfunction "2_2") (pintype "passive"))
      (node (ref "R9") (pin "2") (pinfunction "2_2") (pintype "passive"))
      (node (ref "U7") (pin "3") (pinfunction "IN_3") (pintype "passive"))
      (node (ref "U8") (pin "3") (pinfunction "IN_3") (pintype "passive"))
      (node (ref "UART") (pin "A4") (pinfunction "VBUS_A_A4") (pintype "power_in"))
      (node (ref "UART") (pin "A9") (pinfunction "VBUS_A_A9") (pintype "power_in"))
      (node (ref "UART") (pin "B4") (pinfunction "VBUS_B_B4") (pintype "power_in"))
      (node (ref "UART") (pin "B9") (pinfunction "VBUS_B_B9") (pintype "power_in"))
    )
    (net (code "64") (name "unconnected-(*-IO22-Pad36)") (class "Default")
      (node (ref "*") (pin "36") (pinfunction "IO22_36") (pintype "bidirectional"))
    )
    (net (code "65") (name "unconnected-(*-IO23-Pad37)") (class "Default")
      (node (ref "*") (pin "37") (pinfunction "IO23_37") (pintype "bidirectional"))
    )
    (net (code "66") (name "unconnected-(*-IO34-Pad6)") (class "Default")
      (node (ref "*") (pin "6") (pinfunction "IO34_6") (pintype "input"))
    )
    (net (code "67") (name "unconnected-(*-NC-Pad32)") (class "Default")
      (node (ref "*") (pin "32") (pinfunction "NC_32") (pintype "passive"))
    )
    (net (code "68") (name "unconnected-(*-SCK-Pad20)") (class "Default")
      (node (ref "*") (pin "20") (pinfunction "SCK_20") (pintype "bidirectional"))
    )
    (net (code "69") (name "unconnected-(*-SCS-Pad19)") (class "Default")
      (node (ref "*") (pin "19") (pinfunction "SCS_19") (pintype "bidirectional"))
    )
    (net (code "70") (name "unconnected-(*-SDI-Pad22)") (class "Default")
      (node (ref "*") (pin "22") (pinfunction "SDI_22") (pintype "bidirectional"))
    )
    (net (code "71") (name "unconnected-(*-SDO-Pad21)") (class "Default")
      (node (ref "*") (pin "21") (pinfunction "SDO_21") (pintype "bidirectional"))
    )
    (net (code "72") (name "unconnected-(*-SENSOR_VN-Pad5)") (class "Default")
      (node (ref "*") (pin "5") (pinfunction "SENSOR_VN_5") (pintype "input"))
    )
    (net (code "73") (name "unconnected-(*-SENSOR_VP-Pad4)") (class "Default")
      (node (ref "*") (pin "4") (pinfunction "SENSOR_VP_4") (pintype "input"))
    )
    (net (code "74") (name "unconnected-(*-SHD-Pad17)") (class "Default")
      (node (ref "*") (pin "17") (pinfunction "SHD_17") (pintype "bidirectional"))
    )
    (net (code "75") (name "unconnected-(*-SWP-Pad18)") (class "Default")
      (node (ref "*") (pin "18") (pinfunction "SWP_18") (pintype "bidirectional"))
    )
    (net (code "76") (name "unconnected-(IC1-2A-Pad5)") (class "Default")
      (node (ref "IC1") (pin "5") (pinfunction "2A_5") (pintype "passive"))
    )
    (net (code "77") (name "unconnected-(IC1-2OE-Pad4)") (class "Default")
      (node (ref "IC1") (pin "4") (pinfunction "2OE_4") (pintype "passive"))
    )
    (net (code "78") (name "unconnected-(IC1-2Y-Pad6)") (class "Default")
      (node (ref "IC1") (pin "6") (pinfunction "2Y_6") (pintype "passive"))
    )
    (net (code "79") (name "unconnected-(IC1-GND-Pad7)") (class "Default")
      (node (ref "IC1") (pin "7") (pinfunction "GND_7") (pintype "passive"))
    )
    (net (code "80") (name "unconnected-(IC2-CFG1-Pad2)") (class "Default")
      (node (ref "IC2") (pin "2") (pinfunction "CFG1_2") (pintype "passive"))
    )
    (net (code "81") (name "unconnected-(IC2-CFG2-Pad3)") (class "Default")
      (node (ref "IC2") (pin "3") (pinfunction "CFG2_3") (pintype "passive"))
    )
    (net (code "82") (name "unconnected-(IC2-CFG3-Pad9)") (class "Default")
      (node (ref "IC2") (pin "9") (pinfunction "CFG3_9") (pintype "passive"))
    )
    (net (code "83") (name "unconnected-(IC2-PG-Pad10)") (class "Default")
      (node (ref "IC2") (pin "10") (pinfunction "PG_10") (pintype "passive"))
    )
    (net (code "84") (name "unconnected-(U1-NC-Pad7)") (class "Default")
      (node (ref "U1") (pin "7") (pinfunction "NC_7") (pintype "passive"))
    )
    (net (code "85") (name "unconnected-(U3-Pad3)") (class "Default")
      (node (ref "U3") (pin "3") (pintype "passive"))
    )
    (net (code "86") (name "unconnected-(U3-Pad5)") (class "Default")
      (node (ref "U3") (pin "5") (pintype "passive"))
    )
    (net (code "87") (name "unconnected-(U5-S1C-Pad8)") (class "Default")
      (node (ref "U5") (pin "8") (pinfunction "S1C_8") (pintype "passive"))
    )
    (net (code "88") (name "unconnected-(U6-RTS#-Pad4)") (class "Default")
      (node (ref "U6") (pin "4") (pinfunction "RTS#_4") (pintype "passive"))
    )
    (net (code "89") (name "unconnected-(UART-SBU1-PadA8)") (class "Default")
      (node (ref "UART") (pin "A8") (pinfunction "SBU1_A8") (pintype "bidirectional"))
    )
    (net (code "90") (name "unconnected-(UART-SBU2-PadB8)") (class "Default")
      (node (ref "UART") (pin "B8") (pinfunction "SBU2_B8") (pintype "bidirectional"))
    )
  )
)
